# Amplifier_2.net
KiCad netlist of a schematic drawn in Altium Designer
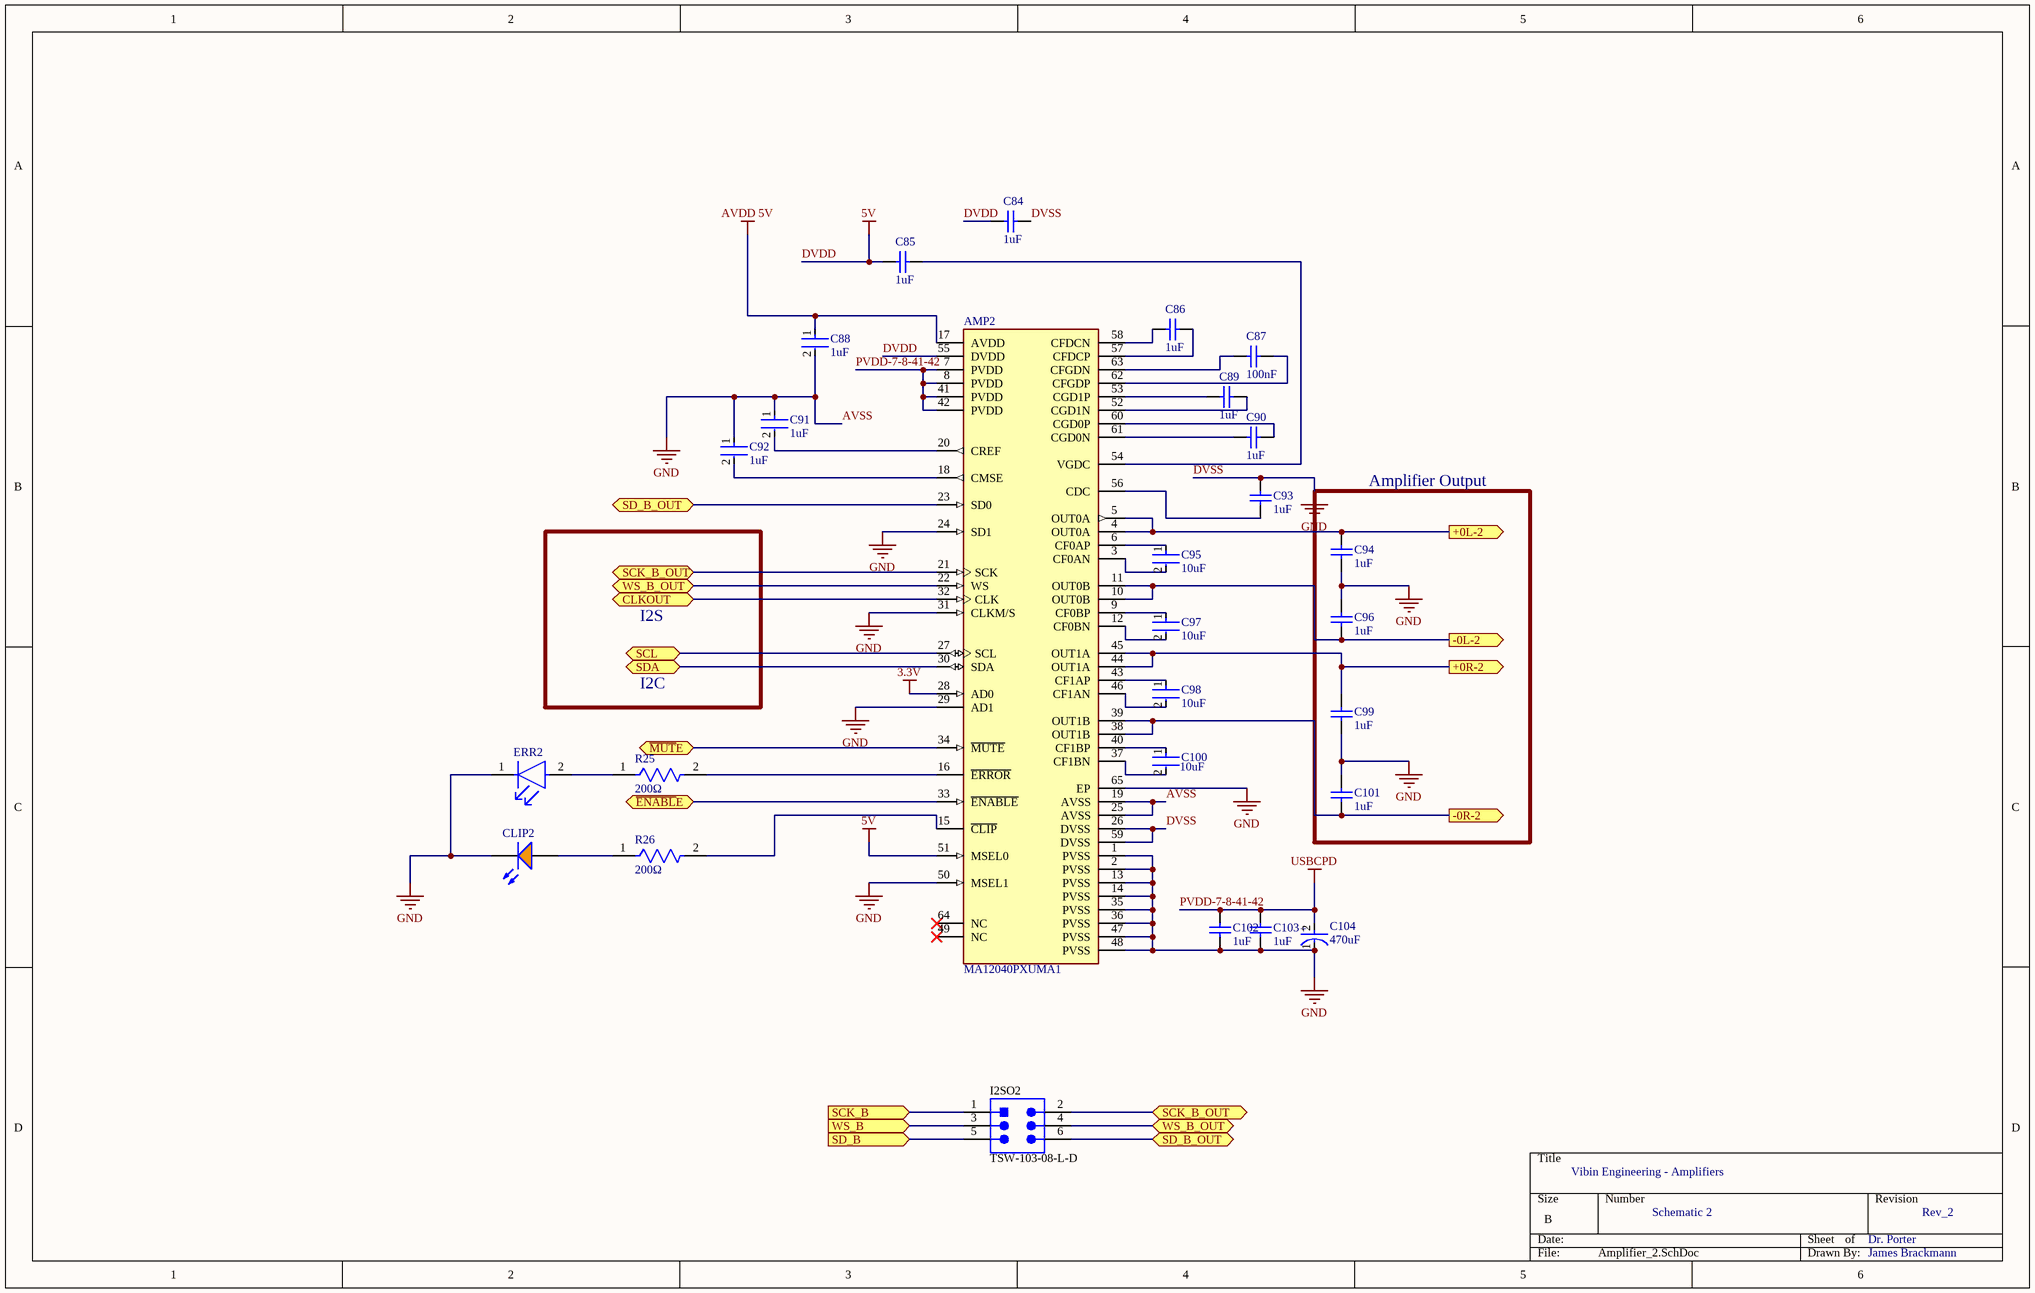
[diagram p0: Amplifier_2.SchDoc]

(export (version "E")
  (design (tool "Eeschema 10.0.6"))
  (components
    (comp (ref "AMP2")
      (value "MA12040PXUMA1")
      (footprint "FP-PG-VQFN-64-IPC_B")
      (description "IC AMP CLASS D STEREO 40W 64QFN")
      (fields
        (field (name "MANUFACTURER") "Infineon")
        (field (name "OCTOPART") "https://octopart.com/ma12040pxuma1-infineon-95984592")
      )
      (libsource (lib "Altium Content Vault") (part "7beef1d240aa861170d3bde7275adf3"))
    )
    (comp (ref "C84")
      (value "1uF")
      (footprint "CAPC1608X90X35LL15T15")
      (description "C0603C105K4RACTU")
      (fields (field (name "MANUFACTURER") "Kemet"))
      (libsource (lib "Altium Content Vault") (part "CAP"))
    )
    (comp (ref "C85")
      (value "1uF")
      (footprint "CAPC1608X90X35LL15T15")
      (description "C0603C105K4RACTU")
      (fields (field (name "MANUFACTURER") "Kemet"))
      (libsource (lib "Altium Content Vault") (part "CAP"))
    )
    (comp (ref "C86")
      (value "1uF")
      (footprint "CAPC1608X90X35LL15T15")
      (description "C0603C105K4RACTU")
      (fields (field (name "MANUFACTURER") "Kemet"))
      (libsource (lib "Altium Content Vault") (part "CAP"))
    )
    (comp (ref "C87")
      (value "100nF")
      (footprint "CAPC1608X90X35ML10T15")
      (fields
        (field (name "TOLERANCE") "10%")
        (field (name "VOLTAGE") "50V")
        (field (name "MANUFACTURER") "Murata")
      )
      (libsource (lib "Altium Content Vault") (part "CAP-NP-2"))
    )
    (comp (ref "C88")
      (value "1uF")
      (footprint "FP-GRM15-0_1-MFG")
      (description "CAP CER 1UF 10V X5R 0402         GRM155R61A105KE15D")
      (fields
        (field (name "OCTOPART") "https://octopart.com/grm155r61a105ke15d-murata-197442")
        (field (name "MANUFACTURER PART NUMBER") "GRM155R61A105KE15D")
      )
      (libsource (lib "Altium Content Vault") (part "02cd4be3c70576c341d710602a673aa"))
    )
    (comp (ref "C89")
      (value "1uF")
      (footprint "CAPC1608X90X35LL15T15")
      (description "C0603C105K4RACTU")
      (fields (field (name "MANUFACTURER") "Kemet"))
      (libsource (lib "Altium Content Vault") (part "CAP"))
    )
    (comp (ref "C90")
      (value "1uF")
      (footprint "CAPC1608X90X35LL15T15")
      (description "C0603C105K4RACTU")
      (fields (field (name "MANUFACTURER") "Kemet"))
      (libsource (lib "Altium Content Vault") (part "CAP"))
    )
    (comp (ref "C91")
      (value "1uF")
      (footprint "FP-GRM15-0_1-MFG")
      (description "CAP CER 1UF 10V X5R 0402         GRM155R61A105KE15D")
      (fields
        (field (name "OCTOPART") "https://octopart.com/grm155r61a105ke15d-murata-197442")
        (field (name "MANUFACTURER PART NUMBER") "GRM155R61A105KE15D")
      )
      (libsource (lib "Altium Content Vault") (part "02cd4be3c70576c341d710602a673aa"))
    )
    (comp (ref "C92")
      (value "1uF")
      (footprint "FP-GRM15-0_1-MFG")
      (description "CAP CER 1UF 10V X5R 0402         GRM155R61A105KE15D")
      (fields
        (field (name "OCTOPART") "https://octopart.com/grm155r61a105ke15d-murata-197442")
        (field (name "MANUFACTURER PART NUMBER") "GRM155R61A105KE15D")
      )
      (libsource (lib "Altium Content Vault") (part "02cd4be3c70576c341d710602a673aa"))
    )
    (comp (ref "C93")
      (value "1uF")
      (footprint "CAPC1608X90X35LL15T15")
      (description "C0603C105K4RACTU")
      (fields (field (name "MANUFACTURER") "Kemet"))
      (libsource (lib "Altium Content Vault") (part "CAP"))
    )
    (comp (ref "C94")
      (value "1uF")
      (footprint "CAPC1608X90X35LL15T15")
      (description "C0603C105K4RACTU")
      (fields (field (name "MANUFACTURER") "Kemet"))
      (libsource (lib "Altium Content Vault") (part "CAP"))
    )
    (comp (ref "C95")
      (value "10uF")
      (footprint "FP-1210-L_3_3_0_4-W_2_5_0-MFG")
      (description "General Purpose Ceramic Capacitor, 1210, 10uF, 10%, X5R, 15%, 25V        12103D106KAT2A")
      (fields (field (name "VOLTAGE") "25V") (field (name "TOLERANCE") "10%"))
      (libsource (lib "Altium Content Vault") (part "b4654b650e69147ec39a6b967a45e02"))
    )
    (comp (ref "C96")
      (value "1uF")
      (footprint "CAPC1608X90X35LL15T15")
      (description "C0603C105K4RACTU")
      (fields (field (name "MANUFACTURER") "Kemet"))
      (libsource (lib "Altium Content Vault") (part "CAP"))
    )
    (comp (ref "C97")
      (value "10uF")
      (footprint "FP-1210-L_3_3_0_4-W_2_5_0-MFG")
      (description "General Purpose Ceramic Capacitor, 1210, 10uF, 10%, X5R, 15%, 25V        12103D106KAT2A")
      (fields (field (name "VOLTAGE") "25V") (field (name "TOLERANCE") "10%"))
      (libsource (lib "Altium Content Vault") (part "b4654b650e69147ec39a6b967a45e02"))
    )
    (comp (ref "C98")
      (value "10uF")
      (footprint "FP-1210-L_3_3_0_4-W_2_5_0-MFG")
      (description "General Purpose Ceramic Capacitor, 1210, 10uF, 10%, X5R, 15%, 25V        12103D106KAT2A")
      (fields (field (name "VOLTAGE") "25V") (field (name "TOLERANCE") "10%"))
      (libsource (lib "Altium Content Vault") (part "b4654b650e69147ec39a6b967a45e02"))
    )
    (comp (ref "C99")
      (value "1uF")
      (footprint "CAPC1608X90X35LL15T15")
      (description "C0603C105K4RACTU")
      (fields (field (name "MANUFACTURER") "Kemet"))
      (libsource (lib "Altium Content Vault") (part "CAP"))
    )
    (comp (ref "C100")
      (value "10uF")
      (footprint "FP-1210-L_3_3_0_4-W_2_5_0-MFG")
      (description "General Purpose Ceramic Capacitor, 1210, 10uF, 10%, X5R, 15%, 25V        12103D106KAT2A")
      (fields (field (name "VOLTAGE") "25V") (field (name "TOLERANCE") "10%"))
      (libsource (lib "Altium Content Vault") (part "b4654b650e69147ec39a6b967a45e02"))
    )
    (comp (ref "C101")
      (value "1uF")
      (footprint "CAPC1608X90X35LL15T15")
      (description "C0603C105K4RACTU")
      (fields (field (name "MANUFACTURER") "Kemet"))
      (libsource (lib "Altium Content Vault") (part "CAP"))
    )
    (comp (ref "C102")
      (value "1uF")
      (footprint "CAPC1608X90X35LL15T15")
      (description "C0603C105K4RACTU")
      (fields (field (name "MANUFACTURER") "Kemet"))
      (libsource (lib "Altium Content Vault") (part "CAP"))
    )
    (comp (ref "C103")
      (value "1uF")
      (footprint "CAPC1608X90X35LL15T15")
      (description "C0603C105K4RACTU")
      (fields (field (name "MANUFACTURER") "Kemet"))
      (libsource (lib "Altium Content Vault") (part "CAP"))
    )
    (comp (ref "C104")
      (value "470uF")
      (footprint "FP-OS-CON-SMT-E12-MFG")
      (description "Conductive Polymer Aluminum Solid Capacitors (OS-CON) 470uF ±20% 20V      20SVPK470M")
      (fields (field (name "TOLERANCE") "20%"))
      (libsource (lib "Altium Content Vault") (part "a00bbbee19879c290e62620ae7e47b1"))
    )
    (comp (ref "CLIP2")
      (value "TLMO1100-GS08")
      (footprint "VISH-TLMX1100-2_V")
      (libsource (lib "Altium Content Vault") (part "LED-ORANGE-AK-2"))
    )
    (comp (ref "ERR2")
      (value "LTST-C190GKT")
      (footprint "FP-LTST-C190GKT-MFG")
      (description "LED GREEN CLEAR CHIP SMD       LTST-C190GKT")
      (fields (field (name "VOLTAGE") "2V"))
      (libsource (lib "Altium Content Vault") (part "8706943c75ba83719d021d2fdc84c58"))
    )
    (comp (ref "I2SO2")
      (value "TSW-103-08-L-D")
      (footprint "SMTC-TSW-103-08-L-D_V")
      (fields (field (name "MANUFACTURER") "Samtec"))
      (libsource (lib "Altium Content Vault") (part "CN-2P-M-R6"))
    )
    (comp (ref "R25")
      (value "200Ω")
      (footprint "FP-ERJ2RK-IPC_A")
      (description "RES SMD 200 OHM 1% 1/10W 0402      ERJ-2RKF2000X")
      (fields (field (name "TOLERANCE") "1%"))
      (libsource (lib "Altium Content Vault") (part "1029c3af85768c4190bb7ad29bc67b5"))
    )
    (comp (ref "R26")
      (value "200Ω")
      (footprint "FP-ERJ2RK-IPC_A")
      (description "RES SMD 200 OHM 1% 1/10W 0402    ERJ-2RKF2000X")
      (fields (field (name "TOLERANCE") "1%"))
      (libsource (lib "Altium Content Vault") (part "1029c3af85768c4190bb7ad29bc67b5"))
    )
  )
  (nets
    (net (code "1") (name "/+0L-2") (class "Default")
      (node (ref "AMP2") (pin "4") (pinfunction "OUT0A_4") (pintype "passive"))
      (node (ref "AMP2") (pin "5") (pinfunction "OUT0A_5") (pintype "output"))
      (node (ref "C94") (pin "1") (pinfunction "1_1") (pintype "passive"))
    )
    (net (code "2") (name "/+0R-2") (class "Default")
      (node (ref "AMP2") (pin "44") (pinfunction "OUT1A_44") (pintype "passive"))
      (node (ref "AMP2") (pin "45") (pinfunction "OUT1A_45") (pintype "passive"))
      (node (ref "C99") (pin "1") (pinfunction "1_1") (pintype "passive"))
    )
    (net (code "3") (name "/-0L-2") (class "Default")
      (node (ref "AMP2") (pin "10") (pinfunction "OUT0B_10") (pintype "passive"))
      (node (ref "AMP2") (pin "11") (pinfunction "OUT0B_11") (pintype "passive"))
      (node (ref "C96") (pin "2") (pinfunction "2_2") (pintype "passive"))
    )
    (net (code "4") (name "/-0R-2") (class "Default")
      (node (ref "AMP2") (pin "38") (pinfunction "OUT1B_38") (pintype "passive"))
      (node (ref "AMP2") (pin "39") (pinfunction "OUT1B_39") (pintype "passive"))
      (node (ref "C101") (pin "2") (pinfunction "2_2") (pintype "passive"))
    )
    (net (code "5") (name "/CLKOUT") (class "Default")
      (node (ref "AMP2") (pin "32") (pinfunction "CLK_32") (pintype "input"))
    )
    (net (code "6") (name "/SCK_B") (class "Default")
      (node (ref "I2SO2") (pin "1") (pinfunction "1_1") (pintype "passive"))
    )
    (net (code "7") (name "/SCK_B_OUT") (class "Default")
      (node (ref "AMP2") (pin "21") (pinfunction "SCK_21") (pintype "input"))
      (node (ref "I2SO2") (pin "2") (pinfunction "2_2") (pintype "passive"))
    )
    (net (code "8") (name "/SCL") (class "Default")
      (node (ref "AMP2") (pin "27") (pinfunction "SCL_27") (pintype "bidirectional"))
    )
    (net (code "9") (name "/SDA") (class "Default")
      (node (ref "AMP2") (pin "30") (pinfunction "SDA_30") (pintype "bidirectional"))
    )
    (net (code "10") (name "/SD_B") (class "Default")
      (node (ref "I2SO2") (pin "5") (pinfunction "5_5") (pintype "passive"))
    )
    (net (code "11") (name "/SD_B_OUT") (class "Default")
      (node (ref "AMP2") (pin "23") (pinfunction "SD0_23") (pintype "input"))
      (node (ref "I2SO2") (pin "6") (pinfunction "6_6") (pintype "passive"))
    )
    (net (code "12") (name "/WS_B") (class "Default")
      (node (ref "I2SO2") (pin "3") (pinfunction "3_3") (pintype "passive"))
    )
    (net (code "13") (name "/WS_B_OUT") (class "Default")
      (node (ref "AMP2") (pin "22") (pinfunction "WS_22") (pintype "input"))
      (node (ref "I2SO2") (pin "4") (pinfunction "4_4") (pintype "passive"))
    )
    (net (code "14") (name "/~{ENABL}E") (class "Default")
      (node (ref "AMP2") (pin "33") (pinfunction "~{ENABLE}_33") (pintype "input"))
    )
    (net (code "15") (name "/~{MUT}E") (class "Default")
      (node (ref "AMP2") (pin "34") (pinfunction "~{MUTE}_34") (pintype "input"))
    )
    (net (code "16") (name "3.3V") (class "Default")
      (node (ref "AMP2") (pin "28") (pinfunction "AD0_28") (pintype "input"))
    )
    (net (code "17") (name "5V") (class "Default")
      (node (ref "AMP2") (pin "51") (pinfunction "MSEL0_51") (pintype "input"))
      (node (ref "AMP2") (pin "55") (pinfunction "DVDD_55") (pintype "power_in"))
      (node (ref "C84") (pin "2") (pinfunction "2_2") (pintype "passive"))
      (node (ref "C85") (pin "1") (pinfunction "1_1") (pintype "passive"))
    )
    (net (code "18") (name "AVDD 5V") (class "Default")
      (node (ref "AMP2") (pin "17") (pinfunction "AVDD_17") (pintype "power_in"))
      (node (ref "C88") (pin "1") (pinfunction "1_1") (pintype "passive"))
    )
    (net (code "19") (name "GND") (class "Default")
      (node (ref "AMP2") (pin "1") (pinfunction "PVSS_1") (pintype "power_in"))
      (node (ref "AMP2") (pin "13") (pinfunction "PVSS_13") (pintype "power_in"))
      (node (ref "AMP2") (pin "14") (pinfunction "PVSS_14") (pintype "power_in"))
      (node (ref "AMP2") (pin "19") (pinfunction "AVSS_19") (pintype "power_in"))
      (node (ref "AMP2") (pin "2") (pinfunction "PVSS_2") (pintype "power_in"))
      (node (ref "AMP2") (pin "24") (pinfunction "SD1_24") (pintype "input"))
      (node (ref "AMP2") (pin "25") (pinfunction "AVSS_25") (pintype "power_in"))
      (node (ref "AMP2") (pin "26") (pinfunction "DVSS_26") (pintype "power_in"))
      (node (ref "AMP2") (pin "29") (pinfunction "AD1_29") (pintype "passive"))
      (node (ref "AMP2") (pin "31") (pinfunction "CLKM/S_31") (pintype "input"))
      (node (ref "AMP2") (pin "35") (pinfunction "PVSS_35") (pintype "power_in"))
      (node (ref "AMP2") (pin "36") (pinfunction "PVSS_36") (pintype "power_in"))
      (node (ref "AMP2") (pin "47") (pinfunction "PVSS_47") (pintype "power_in"))
      (node (ref "AMP2") (pin "48") (pinfunction "PVSS_48") (pintype "power_in"))
      (node (ref "AMP2") (pin "50") (pinfunction "MSEL1_50") (pintype "input"))
      (node (ref "AMP2") (pin "59") (pinfunction "DVSS_59") (pintype "power_in"))
      (node (ref "AMP2") (pin "65") (pinfunction "EP_65") (pintype "power_in"))
      (node (ref "C101") (pin "1") (pinfunction "1_1") (pintype "passive"))
      (node (ref "C102") (pin "2") (pinfunction "2_2") (pintype "passive"))
      (node (ref "C103") (pin "2") (pinfunction "2_2") (pintype "passive"))
      (node (ref "C104") (pin "1") (pinfunction "C_1") (pintype "passive"))
      (node (ref "C84") (pin "1") (pinfunction "1_1") (pintype "passive"))
      (node (ref "C88") (pin "2") (pinfunction "2_2") (pintype "passive"))
      (node (ref "C91") (pin "1") (pinfunction "1_1") (pintype "passive"))
      (node (ref "C92") (pin "1") (pinfunction "1_1") (pintype "passive"))
      (node (ref "C93") (pin "1") (pinfunction "1_1") (pintype "passive"))
      (node (ref "C94") (pin "2") (pinfunction "2_2") (pintype "passive"))
      (node (ref "C96") (pin "1") (pinfunction "1_1") (pintype "passive"))
      (node (ref "C99") (pin "2") (pinfunction "2_2") (pintype "passive"))
      (node (ref "CLIP2") (pin "2") (pinfunction "K_2") (pintype "passive"))
      (node (ref "ERR2") (pin "1") (pinfunction "C_1") (pintype "passive"))
    )
    (net (code "20") (name "Net-(AMP2-CDC)") (class "Default")
      (node (ref "AMP2") (pin "56") (pinfunction "CDC_56") (pintype "passive"))
      (node (ref "C93") (pin "2") (pinfunction "2_2") (pintype "passive"))
    )
    (net (code "21") (name "Net-(AMP2-CF0AN)") (class "Default")
      (node (ref "AMP2") (pin "3") (pinfunction "CF0AN_3") (pintype "passive"))
      (node (ref "C95") (pin "2") (pinfunction "2_2") (pintype "passive"))
    )
    (net (code "22") (name "Net-(AMP2-CF0AP)") (class "Default")
      (node (ref "AMP2") (pin "6") (pinfunction "CF0AP_6") (pintype "passive"))
      (node (ref "C95") (pin "1") (pinfunction "1_1") (pintype "passive"))
    )
    (net (code "23") (name "Net-(AMP2-CF0BN)") (class "Default")
      (node (ref "AMP2") (pin "12") (pinfunction "CF0BN_12") (pintype "passive"))
      (node (ref "C97") (pin "2") (pinfunction "2_2") (pintype "passive"))
    )
    (net (code "24") (name "Net-(AMP2-CF0BP)") (class "Default")
      (node (ref "AMP2") (pin "9") (pinfunction "CF0BP_9") (pintype "passive"))
      (node (ref "C97") (pin "1") (pinfunction "1_1") (pintype "passive"))
    )
    (net (code "25") (name "Net-(AMP2-CF1AN)") (class "Default")
      (node (ref "AMP2") (pin "46") (pinfunction "CF1AN_46") (pintype "passive"))
      (node (ref "C98") (pin "2") (pinfunction "2_2") (pintype "passive"))
    )
    (net (code "26") (name "Net-(AMP2-CF1AP)") (class "Default")
      (node (ref "AMP2") (pin "43") (pinfunction "CF1AP_43") (pintype "passive"))
      (node (ref "C98") (pin "1") (pinfunction "1_1") (pintype "passive"))
    )
    (net (code "27") (name "Net-(AMP2-CF1BN)") (class "Default")
      (node (ref "AMP2") (pin "37") (pinfunction "CF1BN_37") (pintype "passive"))
      (node (ref "C100") (pin "2") (pinfunction "2_2") (pintype "passive"))
    )
    (net (code "28") (name "Net-(AMP2-CF1BP)") (class "Default")
      (node (ref "AMP2") (pin "40") (pinfunction "CF1BP_40") (pintype "passive"))
      (node (ref "C100") (pin "1") (pinfunction "1_1") (pintype "passive"))
    )
    (net (code "29") (name "Net-(AMP2-CFDCN)") (class "Default")
      (node (ref "AMP2") (pin "58") (pinfunction "CFDCN_58") (pintype "passive"))
      (node (ref "C86") (pin "2") (pinfunction "2_2") (pintype "passive"))
    )
    (net (code "30") (name "Net-(AMP2-CFDCP)") (class "Default")
      (node (ref "AMP2") (pin "57") (pinfunction "CFDCP_57") (pintype "passive"))
      (node (ref "C86") (pin "1") (pinfunction "1_1") (pintype "passive"))
    )
    (net (code "31") (name "Net-(AMP2-CFGDN)") (class "Default")
      (node (ref "AMP2") (pin "63") (pinfunction "CFGDN_63") (pintype "passive"))
      (node (ref "C87") (pin "2") (pinfunction "2_2") (pintype "passive"))
    )
    (net (code "32") (name "Net-(AMP2-CFGDP)") (class "Default")
      (node (ref "AMP2") (pin "62") (pinfunction "CFGDP_62") (pintype "passive"))
      (node (ref "C87") (pin "1") (pinfunction "1_1") (pintype "passive"))
    )
    (net (code "33") (name "Net-(AMP2-CGD0N)") (class "Default")
      (node (ref "AMP2") (pin "61") (pinfunction "CGD0N_61") (pintype "passive"))
      (node (ref "C90") (pin "2") (pinfunction "2_2") (pintype "passive"))
    )
    (net (code "34") (name "Net-(AMP2-CGD0P)") (class "Default")
      (node (ref "AMP2") (pin "60") (pinfunction "CGD0P_60") (pintype "passive"))
      (node (ref "C90") (pin "1") (pinfunction "1_1") (pintype "passive"))
    )
    (net (code "35") (name "Net-(AMP2-CGD1N)") (class "Default")
      (node (ref "AMP2") (pin "52") (pinfunction "CGD1N_52") (pintype "passive"))
      (node (ref "C89") (pin "1") (pinfunction "1_1") (pintype "passive"))
    )
    (net (code "36") (name "Net-(AMP2-CGD1P)") (class "Default")
      (node (ref "AMP2") (pin "53") (pinfunction "CGD1P_53") (pintype "passive"))
      (node (ref "C89") (pin "2") (pinfunction "2_2") (pintype "passive"))
    )
    (net (code "37") (name "Net-(AMP2-CMSE)") (class "Default")
      (node (ref "AMP2") (pin "18") (pinfunction "CMSE_18") (pintype "output"))
      (node (ref "C92") (pin "2") (pinfunction "2_2") (pintype "passive"))
    )
    (net (code "38") (name "Net-(AMP2-CREF)") (class "Default")
      (node (ref "AMP2") (pin "20") (pinfunction "CREF_20") (pintype "output"))
      (node (ref "C91") (pin "2") (pinfunction "2_2") (pintype "passive"))
    )
    (net (code "39") (name "Net-(AMP2-VGDC)") (class "Default")
      (node (ref "AMP2") (pin "54") (pinfunction "VGDC_54") (pintype "power_in"))
      (node (ref "C85") (pin "2") (pinfunction "2_2") (pintype "passive"))
    )
    (net (code "40") (name "Net-(AMP2-~{CLIP})") (class "Default")
      (node (ref "AMP2") (pin "15") (pinfunction "~{CLIP}_15") (pintype "open_collector"))
      (node (ref "R26") (pin "2") (pinfunction "2_2") (pintype "passive"))
    )
    (net (code "41") (name "Net-(AMP2-~{ERROR})") (class "Default")
      (node (ref "AMP2") (pin "16") (pinfunction "~{ERROR}_16") (pintype "open_collector"))
      (node (ref "R25") (pin "2") (pinfunction "2_2") (pintype "passive"))
    )
    (net (code "42") (name "Net-(CLIP2-A)") (class "Default")
      (node (ref "CLIP2") (pin "1") (pinfunction "A_1") (pintype "passive"))
      (node (ref "R26") (pin "1") (pinfunction "1_1") (pintype "passive"))
    )
    (net (code "43") (name "Net-(ERR2-A)") (class "Default")
      (node (ref "ERR2") (pin "2") (pinfunction "A_2") (pintype "passive"))
      (node (ref "R25") (pin "1") (pinfunction "1_1") (pintype "passive"))
    )
    (net (code "44") (name "USBCPD") (class "Default")
      (node (ref "AMP2") (pin "41") (pinfunction "PVDD_41") (pintype "power_in"))
      (node (ref "AMP2") (pin "42") (pinfunction "PVDD_42") (pintype "power_in"))
      (node (ref "AMP2") (pin "7") (pinfunction "PVDD_7") (pintype "power_in"))
      (node (ref "AMP2") (pin "8") (pinfunction "PVDD_8") (pintype "power_in"))
      (node (ref "C102") (pin "1") (pinfunction "1_1") (pintype "passive"))
      (node (ref "C103") (pin "1") (pinfunction "1_1") (pintype "passive"))
      (node (ref "C104") (pin "2") (pinfunction "A_2") (pintype "passive"))
    )
    (net (code "45") (name "unconnected-(AMP2-NC-Pad49)") (class "Default")
      (node (ref "AMP2") (pin "49") (pinfunction "NC_49") (pintype "passive+no_connect"))
    )
    (net (code "46") (name "unconnected-(AMP2-NC-Pad64)") (class "Default")
      (node (ref "AMP2") (pin "64") (pinfunction "NC_64") (pintype "passive+no_connect"))
    )
  )
)
